# Schematic.net
KiCad netlist of a schematic drawn in Altium Designer
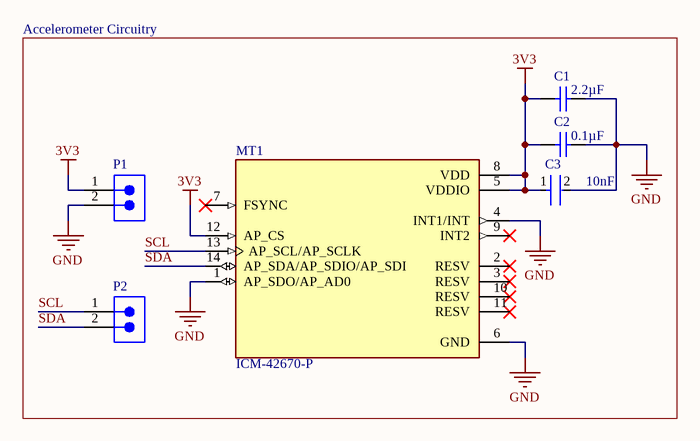
[diagram p0: Schematic.SchDoc]

(export (version "E")
  (design (tool "Eeschema 10.0.6"))
  (components
    (comp (ref "C1")
      (value "2.2µF")
      (footprint "CAPC3216X180X50LL20T25")
      (description "Chip Capacitor, 2.2 uF, +/- 10%, 50 V, -55 to 125 degC, 1206 (3216 Metric), RoHS, Tape and Reel")
      (fields (field (name "MANUFACTURER") "Kemet") (field (name "TOLERANCE") "10%"))
      (libsource (lib "Altium Content Vault") (part "CAP-NP-2"))
    )
    (comp (ref "C2")
      (value "0.1µF")
      (footprint "CAPC3216X100X50LL20T25")
      (description "Chip Capacitor, 100 nF, +/- 10%, 25 V, -55 to 125 degC, 1206 (3216 Metric), RoHS, Tape and Reel")
      (fields (field (name "MANUFACTURER") "Kemet"))
      (libsource (lib "") (part "CAP-NP-2_1"))
    )
    (comp (ref "C3")
      (value "10nF")
      (footprint "FP-C1206C-EB-MFG")
      (description "CAP CER 10000PF 100V X7R 1206")
      (fields
        (field (name "OCTOPART") "https://octopart.com/c1206c103j1ractu-kemet-121270")
        (field (name "MANUFACTURER") "KEMET")
      )
      (libsource (lib "Altium Content Vault") (part "b4654b650e69147ec39a6b967a45e02"))
    )
    (comp (ref "MT1")
      (value "ICM-42670-P")
      (footprint "XDCR_ICM-42670-P")
      (libsource (lib "ICM-42670-P") (part "ICM-42670-P"))
    )
    (comp (ref "P1")
      (value "61300211121")
      (footprint "61300211121")
      (libsource (lib "Altium Content Vault") (part "Header_Male_1R_02P"))
    )
    (comp (ref "P2")
      (value "61300211121")
      (footprint "61300211121")
      (libsource (lib "Altium Content Vault") (part "Header_Male_1R_02P"))
    )
  )
  (nets
    (net (code "1") (name "/SCL") (class "Default")
      (node (ref "MT1") (pin "13") (pinfunction "AP_SCL/AP_SCLK_13") (pintype "input"))
      (node (ref "P2") (pin "1") (pinfunction "1_1") (pintype "passive"))
    )
    (net (code "2") (name "/SDA") (class "Default")
      (node (ref "MT1") (pin "14") (pinfunction "AP_SDA/AP_SDIO/AP_SDI_14") (pintype "bidirectional"))
      (node (ref "P2") (pin "2") (pinfunction "2_2") (pintype "passive"))
    )
    (net (code "3") (name "3V3") (class "Default")
      (node (ref "C1") (pin "2") (pinfunction "2_2") (pintype "passive"))
      (node (ref "C2") (pin "2") (pinfunction "2_2") (pintype "passive"))
      (node (ref "C3") (pin "1") (pinfunction "1_1") (pintype "passive"))
      (node (ref "MT1") (pin "12") (pinfunction "AP_CS_12") (pintype "input"))
      (node (ref "MT1") (pin "5") (pinfunction "VDDIO_5") (pintype "power_in"))
      (node (ref "MT1") (pin "8") (pinfunction "VDD_8") (pintype "power_in"))
      (node (ref "P1") (pin "1") (pinfunction "1_1") (pintype "passive"))
    )
    (net (code "4") (name "GND") (class "Default")
      (node (ref "C1") (pin "1") (pinfunction "1_1") (pintype "passive"))
      (node (ref "C2") (pin "1") (pinfunction "1_1") (pintype "passive"))
      (node (ref "C3") (pin "2") (pinfunction "2_2") (pintype "passive"))
      (node (ref "MT1") (pin "1") (pinfunction "AP_SDO/AP_AD0_1") (pintype "bidirectional"))
      (node (ref "MT1") (pin "4") (pinfunction "INT1/INT_4") (pintype "output"))
      (node (ref "MT1") (pin "6") (pinfunction "GND_6") (pintype "power_in"))
      (node (ref "P1") (pin "2") (pinfunction "2_2") (pintype "passive"))
    )
    (net (code "5") (name "unconnected-(MT1-FSYNC-Pad7)") (class "Default")
      (node (ref "MT1") (pin "7") (pinfunction "FSYNC_7") (pintype "input+no_connect"))
    )
    (net (code "6") (name "unconnected-(MT1-INT2-Pad9)") (class "Default")
      (node (ref "MT1") (pin "9") (pinfunction "INT2_9") (pintype "output+no_connect"))
    )
    (net (code "7") (name "unconnected-(MT1-RESV-Pad2)") (class "Default")
      (node (ref "MT1") (pin "2") (pinfunction "RESV_2") (pintype "passive+no_connect"))
    )
    (net (code "8") (name "unconnected-(MT1-RESV-Pad3)") (class "Default")
      (node (ref "MT1") (pin "3") (pinfunction "RESV_3") (pintype "passive+no_connect"))
    )
    (net (code "9") (name "unconnected-(MT1-RESV-Pad10)") (class "Default")
      (node (ref "MT1") (pin "10") (pinfunction "RESV_10") (pintype "passive+no_connect"))
    )
    (net (code "10") (name "unconnected-(MT1-RESV-Pad11)") (class "Default")
      (node (ref "MT1") (pin "11") (pinfunction "RESV_11") (pintype "passive+no_connect"))
    )
  )
)
